# Connector.net
KiCad netlist of a schematic drawn in Altium Designer
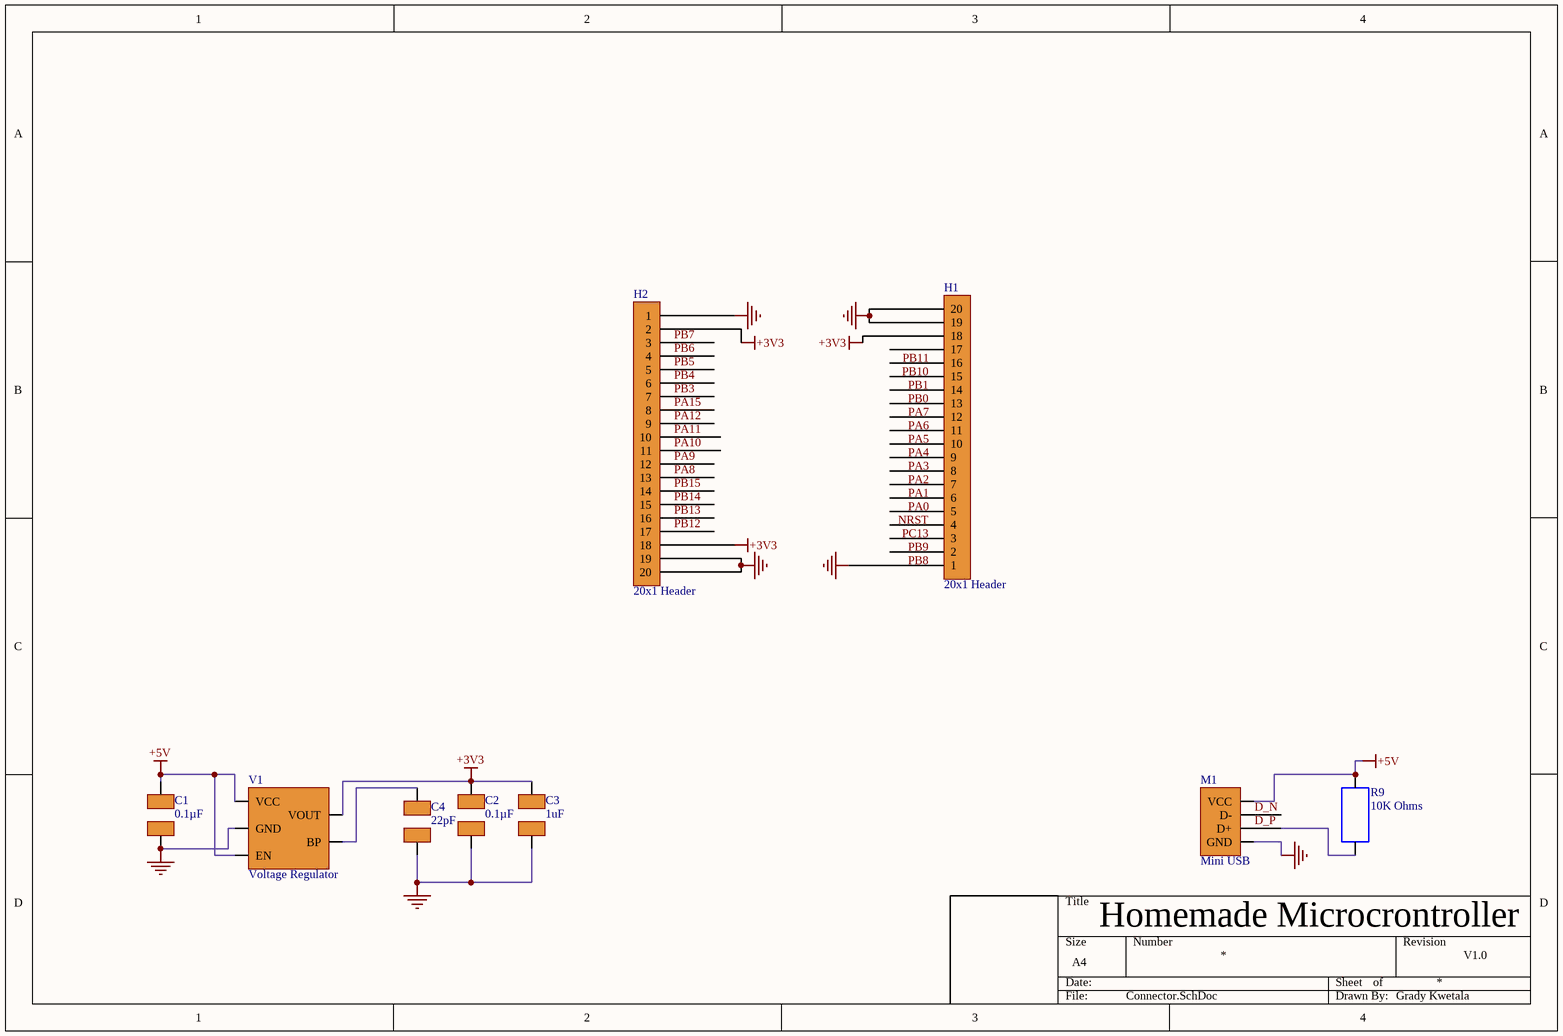
[diagram p0: Connector.SchDoc]

(export (version "E")
  (design (tool "Eeschema 10.0.6"))
  (components
    (comp (ref "C1")
      (value "0.1µF")
      (footprint "capacitor")
      (fields
        (field (name "MANUFACTURER") "KEMET")
        (field (name "MANUFACTURER PART NUMBER") "C0805C104J5RACTU")
        (field (name "TOLERANCE") "5%")
      )
      (libsource (lib "Schematic Library") (part "C0805C104J5RACTU"))
    )
    (comp (ref "C2")
      (value "0.1µF")
      (footprint "capacitor")
      (fields
        (field (name "MANUFACTURER") "KEMET")
        (field (name "MANUFACTURER PART NUMBER") "C0805C104J5RACTU")
        (field (name "TOLERANCE") "5%")
      )
      (libsource (lib "Schematic Library") (part "C0805C104J5RACTU"))
    )
    (comp (ref "C3")
      (value "1uF")
      (footprint "capacitor")
      (description "Cap Ceramic 1uF 50V X7R 10% Pad SMD 0805 125C Automotive T/R")
      (fields
        (field (name "MANUFACTURER") "Murata")
        (field (name "MANUFACTURER PART NUMBER") "GCM21BR71H105KA03K")
      )
      (libsource (lib "Schematic Library") (part "GCM21BR71H105KA03K"))
    )
    (comp (ref "C4")
      (value "22pF")
      (footprint "capacitor")
      (description "Capacitor: ceramic; MLCC; 22pF; 50VDC; C0G; ±5%; SMD; 0805")
      (fields
        (field (name "MANUFACTURER") "KEMET")
        (field (name "MANUFACTURER PART NUMBER") "C0805C220J5GACTU")
      )
      (libsource (lib "Schematic Library") (part "C0805C220J5GACTU"))
    )
    (comp (ref "H1")
      (value "20x1 Header")
      (footprint "20 Pin Header")
      (description "CONN HEADER VERT 40POS 2.54MM")
      (fields
        (field (name "MANUFACTURER") "Wurth Electronics")
        (field (name "MANUFACTURER PART NUMBER") "61304011121")
      )
      (libsource (lib "Schematic Library") (part "61304011121"))
    )
    (comp (ref "H2")
      (value "20x1 Header")
      (footprint "20 Pin Header")
      (description "CONN HEADER VERT 40POS 2.54MM")
      (fields
        (field (name "MANUFACTURER") "Wurth Electronics")
        (field (name "MANUFACTURER PART NUMBER") "61304011121")
      )
      (libsource (lib "") (part "61304011121_1"))
    )
    (comp (ref "M1")
      (value "Mini USB")
      (footprint "mini USB")
      (description "Conn Mini USB Type B RCP 5 POS 0.8mm Solder RA SMD 5 Terminal 1 Port Embossed T/R")
      (fields (field (name "MANUFACTURER") "Molex") (field (name "MANUFACTURER PART NUMBER") "0548191572"))
      (libsource (lib "Schematic Library") (part "0548191572"))
    )
    (comp (ref "R9")
      (value "10K Ohms")
      (footprint "Resistor")
      (description "RES SMD 10KOHM 0.1% 0.0375W 0603")
      (fields
        (field (name "MANUFACTURER") "Vishay Sfernice")
        (field (name "MANUFACTURER PART NUMBER") "PHT0603Y1002BGT")
      )
      (libsource (lib "Schematic Library") (part "PHT0603Y1002BGT"))
    )
    (comp (ref "V1")
      (value "Voltage Regulator")
      (footprint "Voltage regulator")
      (description "IC REG LINEAR 3.3V 300MA SOT23-5")
      (fields (field (name "MANUFACTURER") "Richtek") (field (name "MANUFACTURER PART NUMBER") "RT9193-33GB"))
      (libsource (lib "Schematic Library") (part "RT9193-33GB"))
    )
  )
  (nets
    (net (code "1") (name "+3V3") (class "Default")
      (node (ref "C2") (pin "2") (pinfunction "2_2") (pintype "passive"))
      (node (ref "C3") (pin "2") (pinfunction "2_2") (pintype "passive"))
      (node (ref "H1") (pin "18") (pinfunction "18_18") (pintype "passive"))
      (node (ref "H2") (pin "18") (pinfunction "18_18") (pintype "passive"))
      (node (ref "H2") (pin "2") (pinfunction "2_2") (pintype "passive"))
      (node (ref "V1") (pin "5") (pinfunction "VOUT_5") (pintype "passive"))
    )
    (net (code "2") (name "+5V") (class "Default")
      (node (ref "C1") (pin "2") (pinfunction "2_2") (pintype "passive"))
      (node (ref "M1") (pin "1") (pinfunction "VCC_1") (pintype "passive"))
      (node (ref "R9") (pin "2") (pinfunction "2_2") (pintype "passive"))
      (node (ref "V1") (pin "1") (pinfunction "VCC_1") (pintype "passive"))
      (node (ref "V1") (pin "3") (pinfunction "EN_3") (pintype "passive"))
    )
    (net (code "3") (name "/D_N") (class "Default")
      (node (ref "M1") (pin "2") (pinfunction "D-_2") (pintype "passive"))
    )
    (net (code "4") (name "/D_P") (class "Default")
      (node (ref "M1") (pin "3") (pinfunction "D+_3") (pintype "passive"))
      (node (ref "R9") (pin "1") (pinfunction "1_1") (pintype "passive"))
    )
    (net (code "5") (name "/NRST") (class "Default")
      (node (ref "H1") (pin "5") (pinfunction "5_5") (pintype "passive"))
    )
    (net (code "6") (name "/PA0") (class "Default")
      (node (ref "H1") (pin "6") (pinfunction "6_6") (pintype "passive"))
    )
    (net (code "7") (name "/PA1") (class "Default")
      (node (ref "H1") (pin "7") (pinfunction "7_7") (pintype "passive"))
    )
    (net (code "8") (name "/PA2") (class "Default")
      (node (ref "H1") (pin "8") (pinfunction "8_8") (pintype "passive"))
    )
    (net (code "9") (name "/PA3") (class "Default")
      (node (ref "H1") (pin "9") (pinfunction "9_9") (pintype "passive"))
    )
    (net (code "10") (name "/PA4") (class "Default")
      (node (ref "H1") (pin "10") (pinfunction "10_10") (pintype "passive"))
    )
    (net (code "11") (name "/PA5") (class "Default")
      (node (ref "H1") (pin "11") (pinfunction "11_11") (pintype "passive"))
    )
    (net (code "12") (name "/PA6") (class "Default")
      (node (ref "H1") (pin "12") (pinfunction "12_12") (pintype "passive"))
    )
    (net (code "13") (name "/PA7") (class "Default")
      (node (ref "H1") (pin "13") (pinfunction "13_13") (pintype "passive"))
    )
    (net (code "14") (name "/PA8") (class "Default")
      (node (ref "H2") (pin "13") (pinfunction "13_13") (pintype "passive"))
    )
    (net (code "15") (name "/PA9") (class "Default")
      (node (ref "H2") (pin "12") (pinfunction "12_12") (pintype "passive"))
    )
    (net (code "16") (name "/PA10") (class "Default")
      (node (ref "H2") (pin "11") (pinfunction "11_11") (pintype "passive"))
    )
    (net (code "17") (name "/PA11") (class "Default")
      (node (ref "H2") (pin "10") (pinfunction "10_10") (pintype "passive"))
    )
    (net (code "18") (name "/PA12") (class "Default")
      (node (ref "H2") (pin "9") (pinfunction "9_9") (pintype "passive"))
    )
    (net (code "19") (name "/PA15") (class "Default")
      (node (ref "H2") (pin "8") (pinfunction "8_8") (pintype "passive"))
    )
    (net (code "20") (name "/PB0") (class "Default")
      (node (ref "H1") (pin "14") (pinfunction "14_14") (pintype "passive"))
    )
    (net (code "21") (name "/PB1") (class "Default")
      (node (ref "H1") (pin "15") (pinfunction "15_15") (pintype "passive"))
    )
    (net (code "22") (name "/PB3") (class "Default")
      (node (ref "H2") (pin "7") (pinfunction "7_7") (pintype "passive"))
    )
    (net (code "23") (name "/PB4") (class "Default")
      (node (ref "H2") (pin "6") (pinfunction "6_6") (pintype "passive"))
    )
    (net (code "24") (name "/PB5") (class "Default")
      (node (ref "H2") (pin "5") (pinfunction "5_5") (pintype "passive"))
    )
    (net (code "25") (name "/PB6") (class "Default")
      (node (ref "H2") (pin "4") (pinfunction "4_4") (pintype "passive"))
    )
    (net (code "26") (name "/PB7") (class "Default")
      (node (ref "H2") (pin "3") (pinfunction "3_3") (pintype "passive"))
    )
    (net (code "27") (name "/PB8") (class "Default")
      (node (ref "H1") (pin "2") (pinfunction "2_2") (pintype "passive"))
    )
    (net (code "28") (name "/PB9") (class "Default")
      (node (ref "H1") (pin "3") (pinfunction "3_3") (pintype "passive"))
    )
    (net (code "29") (name "/PB10") (class "Default")
      (node (ref "H1") (pin "16") (pinfunction "16_16") (pintype "passive"))
    )
    (net (code "30") (name "/PB11") (class "Default")
      (node (ref "H1") (pin "17") (pinfunction "17_17") (pintype "passive"))
    )
    (net (code "31") (name "/PB12") (class "Default")
      (node (ref "H2") (pin "17") (pinfunction "17_17") (pintype "passive"))
    )
    (net (code "32") (name "/PB13") (class "Default")
      (node (ref "H2") (pin "16") (pinfunction "16_16") (pintype "passive"))
    )
    (net (code "33") (name "/PB14") (class "Default")
      (node (ref "H2") (pin "15") (pinfunction "15_15") (pintype "passive"))
    )
    (net (code "34") (name "/PB15") (class "Default")
      (node (ref "H2") (pin "14") (pinfunction "14_14") (pintype "passive"))
    )
    (net (code "35") (name "/PC13") (class "Default")
      (node (ref "H1") (pin "4") (pinfunction "4_4") (pintype "passive"))
    )
    (net (code "36") (name "GND") (class "Default")
      (node (ref "C1") (pin "1") (pinfunction "1_1") (pintype "passive"))
      (node (ref "C2") (pin "1") (pinfunction "1_1") (pintype "passive"))
      (node (ref "C3") (pin "1") (pinfunction "1_1") (pintype "passive"))
      (node (ref "C4") (pin "1") (pinfunction "1_1") (pintype "passive"))
      (node (ref "H1") (pin "1") (pinfunction "1_1") (pintype "passive"))
      (node (ref "H1") (pin "19") (pinfunction "19_19") (pintype "passive"))
      (node (ref "H1") (pin "20") (pinfunction "20_20") (pintype "passive"))
      (node (ref "H2") (pin "1") (pinfunction "1_1") (pintype "passive"))
      (node (ref "H2") (pin "19") (pinfunction "19_19") (pintype "passive"))
      (node (ref "H2") (pin "20") (pinfunction "20_20") (pintype "passive"))
      (node (ref "M1") (pin "4") (pinfunction "GND_4") (pintype "passive"))
      (node (ref "V1") (pin "2") (pinfunction "GND_2") (pintype "passive"))
    )
    (net (code "37") (name "Net-(V1-BP)") (class "Default")
      (node (ref "C4") (pin "2") (pinfunction "2_2") (pintype "passive"))
      (node (ref "V1") (pin "4") (pinfunction "BP_4") (pintype "passive"))
    )
  )
)
